# mosfet.net
KiCad netlist of a schematic drawn in Altium Designer
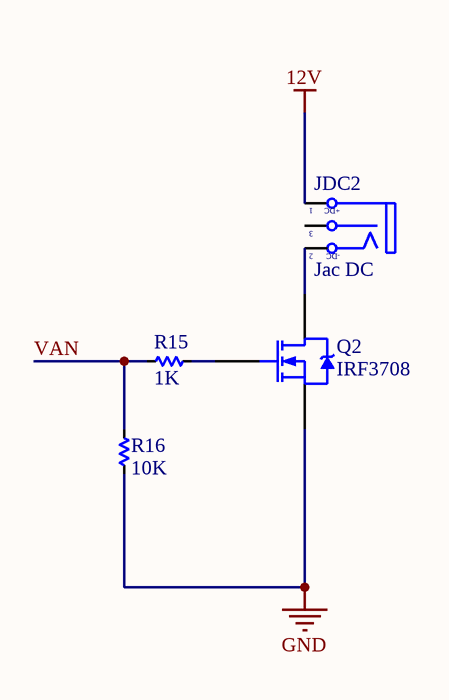
[diagram p0: mosfet.SchDoc]

(export (version "E")
  (design (tool "Eeschema 10.0.6"))
  (components
    (comp (ref "JDC2")
      (value "Jac DC")
      (footprint "DC3")
      (description "Jac DC input")
      (libsource (lib "LIBRARY") (part "DCIN"))
    )
    (comp (ref "Q2")
      (value "IRF3708")
      (footprint "TO-252AA_N")
      (description "HEXFET Power MOSFET")
      (fields (field (name "PUBLISHER") "Altium Limited"))
      (libsource (lib "IR Discrete MOSFET - Power") (part "IRFR3911"))
    )
    (comp (ref "R15")
      (value "1K")
      (footprint "RES-SMD-0805")
      (description "Resistor")
      (fields
        (field (name "MANUFACTURER") "Generic Components")
        (field (name "PUBLISHER") "Altium Hobart Technology Centre")
      )
      (libsource (lib "LIBRARY") (part "Res-SMD"))
    )
    (comp (ref "R16")
      (value "10K")
      (footprint "RES-SMD-0805")
      (description "Resistor")
      (fields
        (field (name "MANUFACTURER") "Generic Components")
        (field (name "PUBLISHER") "Altium Hobart Technology Centre")
      )
      (libsource (lib "LIBRARY") (part "Res-SMD"))
    )
  )
  (nets
    (net (code "1") (name "/VAN") (class "Default")
      (node (ref "R15") (pin "1") (pinfunction "1_1") (pintype "passive"))
      (node (ref "R16") (pin "1") (pinfunction "1_1") (pintype "passive"))
    )
    (net (code "2") (name "12V") (class "Default")
      (node (ref "JDC2") (pin "1") (pinfunction "T_1") (pintype "passive"))
    )
    (net (code "3") (name "GND") (class "Default")
      (node (ref "Q2") (pin "3") (pinfunction "S_3") (pintype "passive"))
      (node (ref "R16") (pin "2") (pinfunction "2_2") (pintype "passive"))
    )
    (net (code "4") (name "Net-(JDC2-TN)") (class "Default")
      (node (ref "JDC2") (pin "2") (pinfunction "TN_2") (pintype "passive"))
      (node (ref "Q2") (pin "4") (pinfunction "D_4") (pintype "passive"))
    )
    (net (code "5") (name "Net-(Q2-G)") (class "Default")
      (node (ref "Q2") (pin "1") (pinfunction "G_1") (pintype "passive"))
      (node (ref "R15") (pin "2") (pinfunction "2_2") (pintype "passive"))
    )
    (net (code "6") (name "unconnected-(JDC2-S-Pad3)") (class "Default")
      (node (ref "JDC2") (pin "3") (pinfunction "S_3") (pintype "power_in"))
    )
  )
)
